# SPLITTER.net
KiCad netlist of a schematic drawn in Altium Designer
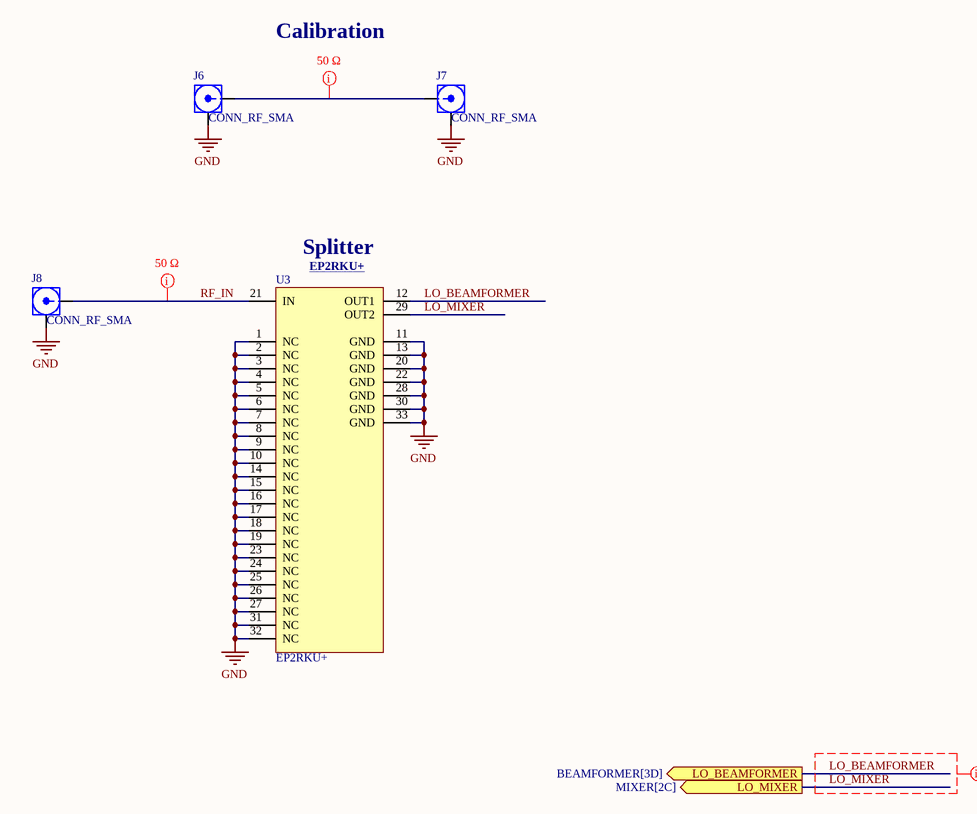
[diagram p0: SPLITTER.SchDoc]

(export (version "E")
  (design (tool "Eeschema 10.0.6"))
  (components
    (comp (ref "J6")
      (value "CONN_RF_SMA")
      (footprint "142-0701-801")
      (description "RF / Coaxial Connector, SMA Coaxial, Straight Jack, Solder, 50 ohm, Beryllium Copper")
      (fields
        (field (name "MANUFACTURER") "Cinch Connectivity Solutions Johnson")
        (field (name "MANUFACTURER PART NUMBER") "142-0701-801")
      )
      (libsource (lib "Titan") (part "CONN_RF_SMA"))
    )
    (comp (ref "J7")
      (value "CONN_RF_SMA")
      (footprint "142-0701-801")
      (description "RF / Coaxial Connector, SMA Coaxial, Straight Jack, Solder, 50 ohm, Beryllium Copper")
      (fields
        (field (name "MANUFACTURER") "Cinch Connectivity Solutions Johnson")
        (field (name "MANUFACTURER PART NUMBER") "142-0701-801")
      )
      (libsource (lib "Titan") (part "CONN_RF_SMA"))
    )
    (comp (ref "J8")
      (value "CONN_RF_SMA")
      (footprint "142-0701-801")
      (description "RF / Coaxial Connector, SMA Coaxial, Straight Jack, Solder, 50 ohm, Beryllium Copper")
      (fields
        (field (name "MANUFACTURER") "Cinch Connectivity Solutions Johnson")
        (field (name "MANUFACTURER PART NUMBER") "142-0701-801")
      )
      (libsource (lib "Titan") (part "CONN_RF_SMA"))
    )
    (comp (ref "U3")
      (value "EP2RKU+")
      (footprint "PL-648")
      (description "Splitter And Combiner, 0MHz Min, 18000MHz Max, 3.9dB Insertion Loss-Max, GAAS")
      (fields (field (name "MANUFACTURER") "Mini-Circuits"))
      (libsource (lib "Titan") (part "EP2RKU+"))
    )
  )
  (nets
    (net (code "1") (name "/LO_BEAMFORMER") (class "Default")
      (node (ref "U3") (pin "12") (pinfunction "OUT1_12") (pintype "passive"))
    )
    (net (code "2") (name "/LO_MIXER") (class "Default")
      (node (ref "U3") (pin "29") (pinfunction "OUT2_29") (pintype "passive"))
    )
    (net (code "3") (name "/RF_IN") (class "Default")
      (node (ref "J8") (pin "1") (pintype "passive"))
      (node (ref "U3") (pin "21") (pinfunction "IN_21") (pintype "passive"))
    )
    (net (code "4") (name "GND") (class "Default")
      (node (ref "J6") (pin "2") (pintype "passive"))
      (node (ref "J7") (pin "2") (pintype "passive"))
      (node (ref "J8") (pin "2") (pintype "passive"))
      (node (ref "U3") (pin "1") (pinfunction "NC_1") (pintype "passive"))
      (node (ref "U3") (pin "10") (pinfunction "NC_10") (pintype "passive"))
      (node (ref "U3") (pin "11") (pinfunction "GND_11") (pintype "power_in"))
      (node (ref "U3") (pin "13") (pinfunction "GND_13") (pintype "power_in"))
      (node (ref "U3") (pin "14") (pinfunction "NC_14") (pintype "passive"))
      (node (ref "U3") (pin "15") (pinfunction "NC_15") (pintype "passive"))
      (node (ref "U3") (pin "16") (pinfunction "NC_16") (pintype "passive"))
      (node (ref "U3") (pin "17") (pinfunction "NC_17") (pintype "passive"))
      (node (ref "U3") (pin "18") (pinfunction "NC_18") (pintype "passive"))
      (node (ref "U3") (pin "19") (pinfunction "NC_19") (pintype "passive"))
      (node (ref "U3") (pin "2") (pinfunction "NC_2") (pintype "passive"))
      (node (ref "U3") (pin "20") (pinfunction "GND_20") (pintype "power_in"))
      (node (ref "U3") (pin "22") (pinfunction "GND_22") (pintype "power_in"))
      (node (ref "U3") (pin "23") (pinfunction "NC_23") (pintype "passive"))
      (node (ref "U3") (pin "24") (pinfunction "NC_24") (pintype "passive"))
      (node (ref "U3") (pin "25") (pinfunction "NC_25") (pintype "passive"))
      (node (ref "U3") (pin "26") (pinfunction "NC_26") (pintype "passive"))
      (node (ref "U3") (pin "27") (pinfunction "NC_27") (pintype "passive"))
      (node (ref "U3") (pin "28") (pinfunction "GND_28") (pintype "power_in"))
      (node (ref "U3") (pin "3") (pinfunction "NC_3") (pintype "passive"))
      (node (ref "U3") (pin "30") (pinfunction "GND_30") (pintype "power_in"))
      (node (ref "U3") (pin "31") (pinfunction "NC_31") (pintype "passive"))
      (node (ref "U3") (pin "32") (pinfunction "NC_32") (pintype "passive"))
      (node (ref "U3") (pin "33") (pinfunction "GND_33") (pintype "power_in"))
      (node (ref "U3") (pin "4") (pinfunction "NC_4") (pintype "passive"))
      (node (ref "U3") (pin "5") (pinfunction "NC_5") (pintype "passive"))
      (node (ref "U3") (pin "6") (pinfunction "NC_6") (pintype "passive"))
      (node (ref "U3") (pin "7") (pinfunction "NC_7") (pintype "passive"))
      (node (ref "U3") (pin "8") (pinfunction "NC_8") (pintype "passive"))
      (node (ref "U3") (pin "9") (pinfunction "NC_9") (pintype "passive"))
    )
    (net (code "5") (name "Net-(J6-Pad1)") (class "Default")
      (node (ref "J6") (pin "1") (pintype "passive"))
      (node (ref "J7") (pin "1") (pintype "passive"))
    )
  )
)
